# Downstream_Port.net
KiCad netlist of a schematic drawn in Altium Designer
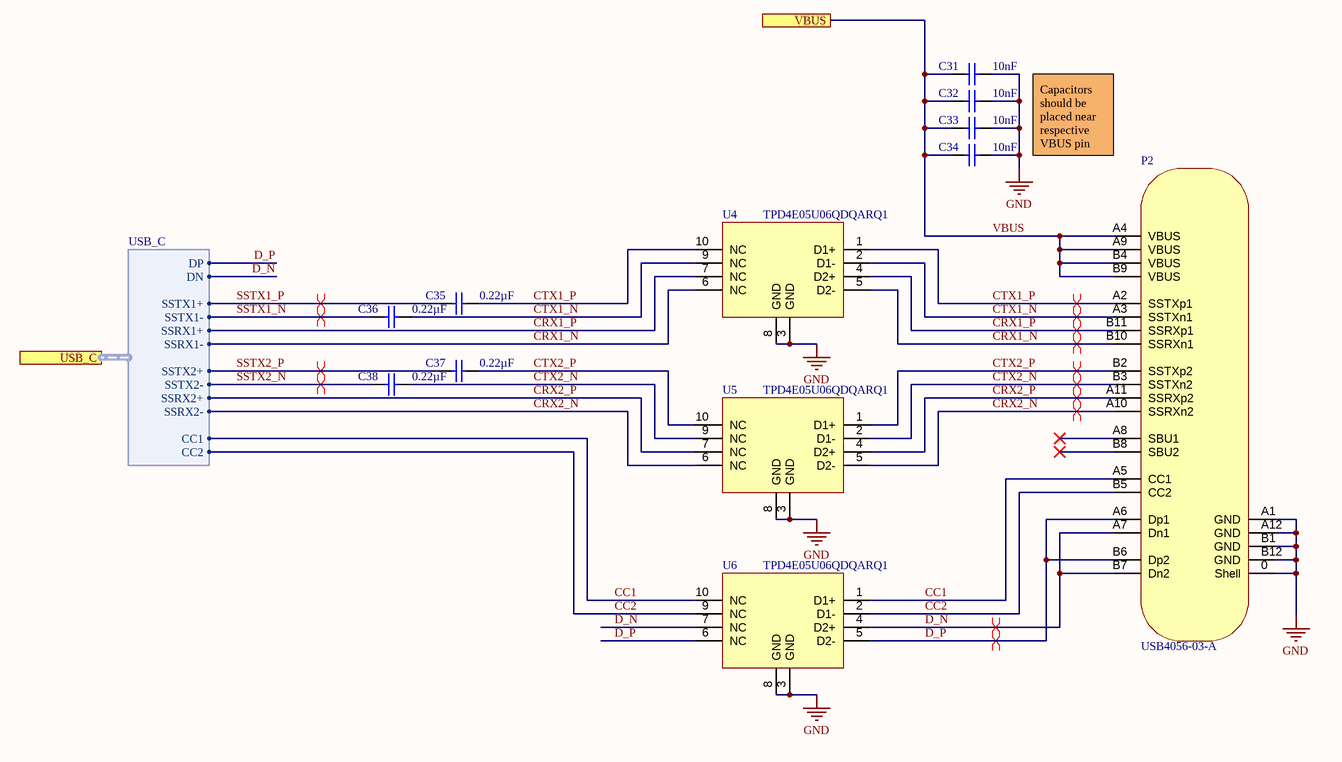
[diagram p0: Downstream_Port.SchDoc]

(export (version "E")
  (design (tool "Eeschema 10.0.6"))
  (components
    (comp (ref "C31")
      (value "10nF")
      (footprint "CAP0402")
      (description "10000 pF ±10% 50V Ceramic Capacitor X7R 0402 (1005 Metric)")
      (fields (field (name "VOLTAGE") "50V") (field (name "Comment") "CC0402KRX7R9BB103"))
      (libsource (lib "Schlib1") (part "CC0402KRX7R9BB103"))
    )
    (comp (ref "C32")
      (value "10nF")
      (footprint "CAP0402")
      (description "10000 pF ±10% 50V Ceramic Capacitor X7R 0402 (1005 Metric)")
      (fields (field (name "VOLTAGE") "50V") (field (name "Comment") "CC0402KRX7R9BB103"))
      (libsource (lib "Schlib1") (part "CC0402KRX7R9BB103"))
    )
    (comp (ref "C33")
      (value "10nF")
      (footprint "CAP0402")
      (description "10000 pF ±10% 50V Ceramic Capacitor X7R 0402 (1005 Metric)")
      (fields (field (name "VOLTAGE") "50V") (field (name "Comment") "CC0402KRX7R9BB103"))
      (libsource (lib "Schlib1") (part "CC0402KRX7R9BB103"))
    )
    (comp (ref "C34")
      (value "10nF")
      (footprint "CAP0402")
      (description "10000 pF ±10% 50V Ceramic Capacitor X7R 0402 (1005 Metric)")
      (fields (field (name "VOLTAGE") "50V") (field (name "Comment") "CC0402KRX7R9BB103"))
      (libsource (lib "Schlib1") (part "CC0402KRX7R9BB103"))
    )
    (comp (ref "C35")
      (value "0.22µF")
      (footprint "CAP0402")
      (description "0.22 µF ±10% 50V Ceramic Capacitor X5R 0402 (1005 Metric)")
      (fields (field (name "VOLTAGE") "50V") (field (name "Comment") "UMK105BJ224KV-F"))
      (libsource (lib "Schlib1") (part "UMK105BJ224KV-F"))
    )
    (comp (ref "C36")
      (value "0.22µF")
      (footprint "CAP0402")
      (description "0.22 µF ±10% 50V Ceramic Capacitor X5R 0402 (1005 Metric)")
      (fields (field (name "VOLTAGE") "50V") (field (name "Comment") "UMK105BJ224KV-F"))
      (libsource (lib "Schlib1") (part "UMK105BJ224KV-F"))
    )
    (comp (ref "C37")
      (value "0.22µF")
      (footprint "CAP0402")
      (description "0.22 µF ±10% 50V Ceramic Capacitor X5R 0402 (1005 Metric)")
      (fields (field (name "VOLTAGE") "50V") (field (name "Comment") "UMK105BJ224KV-F"))
      (libsource (lib "Schlib1") (part "UMK105BJ224KV-F"))
    )
    (comp (ref "C38")
      (value "0.22µF")
      (footprint "CAP0402")
      (description "0.22 µF ±10% 50V Ceramic Capacitor X5R 0402 (1005 Metric)")
      (fields (field (name "VOLTAGE") "50V") (field (name "Comment") "UMK105BJ224KV-F"))
      (libsource (lib "Schlib1") (part "UMK105BJ224KV-F"))
    )
    (comp (ref "P2")
      (value "USB4056-03-A")
      (footprint "USB4056-03-A")
      (fields (field (name "MANUFACTURER") "GCT") (field (name "VOLTAGE") "48VDC"))
      (libsource (lib "Schlib1") (part "USB4056-03-A"))
    )
    (comp (ref "U4")
      (value "TPD4E05U06QDQARQ1")
      (footprint "10-UFDFN")
      (description "14V Clamp 2.5A (8/20µs) Ipp Tvs Diode Surface Mount 10-USON (2.5x1)")
      (fields (field (name "MANUFACTURER") "Texas Instruments"))
      (libsource (lib "Schlib1") (part "TPD4E05U06QDQARQ1"))
    )
    (comp (ref "U5")
      (value "TPD4E05U06QDQARQ1")
      (footprint "10-UFDFN")
      (description "14V Clamp 2.5A (8/20µs) Ipp Tvs Diode Surface Mount 10-USON (2.5x1)")
      (fields (field (name "MANUFACTURER") "Texas Instruments"))
      (libsource (lib "Schlib1") (part "TPD4E05U06QDQARQ1"))
    )
    (comp (ref "U6")
      (value "TPD4E05U06QDQARQ1")
      (footprint "10-UFDFN")
      (description "14V Clamp 2.5A (8/20µs) Ipp Tvs Diode Surface Mount 10-USON (2.5x1)")
      (fields (field (name "MANUFACTURER") "Texas Instruments"))
      (libsource (lib "Schlib1") (part "TPD4E05U06QDQARQ1"))
    )
  )
  (nets
    (net (code "2") (name "/CC1") (class "Default")
      (node (ref "P2") (pin "A5") (pinfunction "CC1_A5") (pintype "passive"))
      (node (ref "U6") (pin "1") (pinfunction "D1+_1") (pintype "passive"))
      (node (ref "U6") (pin "10") (pinfunction "NC_10") (pintype "passive"))
    )
    (net (code "3") (name "/CC2") (class "Default")
      (node (ref "P2") (pin "B5") (pinfunction "CC2_B5") (pintype "passive"))
      (node (ref "U6") (pin "2") (pinfunction "D1-_2") (pintype "passive"))
      (node (ref "U6") (pin "9") (pinfunction "NC_9") (pintype "passive"))
    )
    (net (code "4") (name "/CRX1_N") (class "Default")
      (node (ref "P2") (pin "B10") (pinfunction "SSRXn1_B10") (pintype "passive"))
      (node (ref "U4") (pin "5") (pinfunction "D2-_5") (pintype "passive"))
      (node (ref "U4") (pin "6") (pinfunction "NC_6") (pintype "passive"))
    )
    (net (code "5") (name "/CRX1_P") (class "Default")
      (node (ref "P2") (pin "B11") (pinfunction "SSRXp1_B11") (pintype "passive"))
      (node (ref "U4") (pin "4") (pinfunction "D2+_4") (pintype "passive"))
      (node (ref "U4") (pin "7") (pinfunction "NC_7") (pintype "passive"))
    )
    (net (code "6") (name "/CRX2_N") (class "Default")
      (node (ref "P2") (pin "A10") (pinfunction "SSRXn2_A10") (pintype "passive"))
      (node (ref "U5") (pin "5") (pinfunction "D2-_5") (pintype "passive"))
      (node (ref "U5") (pin "6") (pinfunction "NC_6") (pintype "passive"))
    )
    (net (code "7") (name "/CRX2_P") (class "Default")
      (node (ref "P2") (pin "A11") (pinfunction "SSRXp2_A11") (pintype "passive"))
      (node (ref "U5") (pin "4") (pinfunction "D2+_4") (pintype "passive"))
      (node (ref "U5") (pin "7") (pinfunction "NC_7") (pintype "passive"))
    )
    (net (code "8") (name "/CTX1_N") (class "Default")
      (node (ref "C36") (pin "2") (pinfunction "2_2") (pintype "passive"))
      (node (ref "P2") (pin "A3") (pinfunction "SSTXn1_A3") (pintype "passive"))
      (node (ref "U4") (pin "2") (pinfunction "D1-_2") (pintype "passive"))
      (node (ref "U4") (pin "9") (pinfunction "NC_9") (pintype "passive"))
    )
    (net (code "9") (name "/CTX1_P") (class "Default")
      (node (ref "C35") (pin "2") (pinfunction "2_2") (pintype "passive"))
      (node (ref "P2") (pin "A2") (pinfunction "SSTXp1_A2") (pintype "passive"))
      (node (ref "U4") (pin "1") (pinfunction "D1+_1") (pintype "passive"))
      (node (ref "U4") (pin "10") (pinfunction "NC_10") (pintype "passive"))
    )
    (net (code "10") (name "/CTX2_N") (class "Default")
      (node (ref "C38") (pin "2") (pinfunction "2_2") (pintype "passive"))
      (node (ref "P2") (pin "B3") (pinfunction "SSTXn2_B3") (pintype "passive"))
      (node (ref "U5") (pin "2") (pinfunction "D1-_2") (pintype "passive"))
      (node (ref "U5") (pin "9") (pinfunction "NC_9") (pintype "passive"))
    )
    (net (code "11") (name "/CTX2_P") (class "Default")
      (node (ref "C37") (pin "2") (pinfunction "2_2") (pintype "passive"))
      (node (ref "P2") (pin "B2") (pinfunction "SSTXp2_B2") (pintype "passive"))
      (node (ref "U5") (pin "1") (pinfunction "D1+_1") (pintype "passive"))
      (node (ref "U5") (pin "10") (pinfunction "NC_10") (pintype "passive"))
    )
    (net (code "12") (name "/D_N") (class "Default")
      (node (ref "P2") (pin "A7") (pinfunction "Dn1_A7") (pintype "passive"))
      (node (ref "P2") (pin "B7") (pinfunction "Dn2_B7") (pintype "passive"))
      (node (ref "U6") (pin "4") (pinfunction "D2+_4") (pintype "passive"))
      (node (ref "U6") (pin "7") (pinfunction "NC_7") (pintype "passive"))
    )
    (net (code "13") (name "/D_P") (class "Default")
      (node (ref "P2") (pin "A6") (pinfunction "Dp1_A6") (pintype "passive"))
      (node (ref "P2") (pin "B6") (pinfunction "Dp2_B6") (pintype "passive"))
      (node (ref "U6") (pin "5") (pinfunction "D2-_5") (pintype "passive"))
      (node (ref "U6") (pin "6") (pinfunction "NC_6") (pintype "passive"))
    )
    (net (code "14") (name "/SSTX1_N") (class "Default")
      (node (ref "C36") (pin "1") (pinfunction "1_1") (pintype "passive"))
    )
    (net (code "15") (name "/SSTX1_P") (class "Default")
      (node (ref "C35") (pin "1") (pinfunction "1_1") (pintype "passive"))
    )
    (net (code "16") (name "/SSTX2_N") (class "Default")
      (node (ref "C38") (pin "1") (pinfunction "1_1") (pintype "passive"))
    )
    (net (code "17") (name "/SSTX2_P") (class "Default")
      (node (ref "C37") (pin "1") (pinfunction "1_1") (pintype "passive"))
    )
    (net (code "18") (name "/VBUS") (class "Default")
      (node (ref "C31") (pin "2") (pinfunction "2_2") (pintype "passive"))
      (node (ref "C32") (pin "2") (pinfunction "2_2") (pintype "passive"))
      (node (ref "C33") (pin "2") (pinfunction "2_2") (pintype "passive"))
      (node (ref "C34") (pin "2") (pinfunction "2_2") (pintype "passive"))
      (node (ref "P2") (pin "A4") (pinfunction "VBUS_A4") (pintype "passive"))
      (node (ref "P2") (pin "A9") (pinfunction "VBUS_A9") (pintype "passive"))
      (node (ref "P2") (pin "B4") (pinfunction "VBUS_B4") (pintype "passive"))
      (node (ref "P2") (pin "B9") (pinfunction "VBUS_B9") (pintype "passive"))
    )
    (net (code "20") (name "GND") (class "Default")
      (node (ref "C31") (pin "1") (pinfunction "1_1") (pintype "passive"))
      (node (ref "C32") (pin "1") (pinfunction "1_1") (pintype "passive"))
      (node (ref "C33") (pin "1") (pinfunction "1_1") (pintype "passive"))
      (node (ref "C34") (pin "1") (pinfunction "1_1") (pintype "passive"))
      (node (ref "P2") (pin "0") (pinfunction "Shell_0") (pintype "passive"))
      (node (ref "P2") (pin "A1") (pinfunction "GND_A1") (pintype "passive"))
      (node (ref "P2") (pin "A12") (pinfunction "GND_A12") (pintype "passive"))
      (node (ref "P2") (pin "B1") (pinfunction "GND_B1") (pintype "passive"))
      (node (ref "P2") (pin "B12") (pinfunction "GND_B12") (pintype "passive"))
      (node (ref "U4") (pin "3") (pinfunction "GND_3") (pintype "passive"))
      (node (ref "U4") (pin "8") (pinfunction "GND_8") (pintype "passive"))
      (node (ref "U5") (pin "3") (pinfunction "GND_3") (pintype "passive"))
      (node (ref "U5") (pin "8") (pinfunction "GND_8") (pintype "passive"))
      (node (ref "U6") (pin "3") (pinfunction "GND_3") (pintype "passive"))
      (node (ref "U6") (pin "8") (pinfunction "GND_8") (pintype "passive"))
    )
    (net (code "21") (name "unconnected-(P2-SBU1-PadA8)") (class "Default")
      (node (ref "P2") (pin "A8") (pinfunction "SBU1_A8") (pintype "passive+no_connect"))
    )
    (net (code "22") (name "unconnected-(P2-SBU2-PadB8)") (class "Default")
      (node (ref "P2") (pin "B8") (pinfunction "SBU2_B8") (pintype "passive+no_connect"))
    )
  )
)
